# Sheet1.net
KiCad netlist of a schematic drawn in Altium Designer
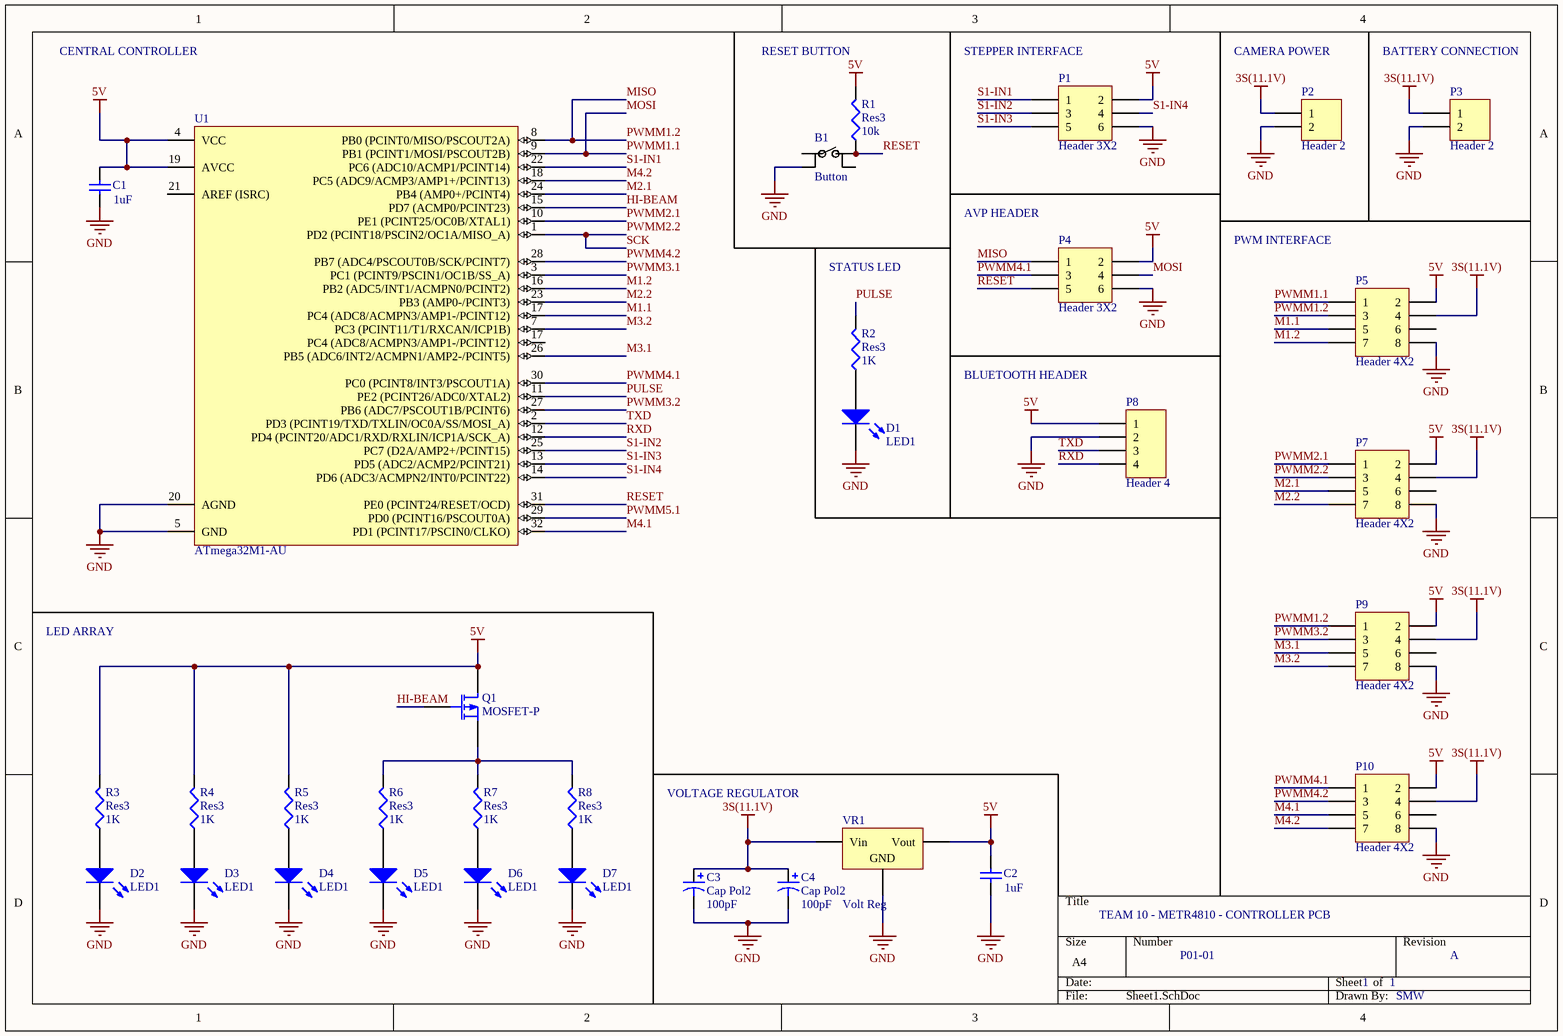
[diagram p0: Sheet1.SchDoc]

(export (version "E")
  (design (tool "Eeschema 10.0.6"))
  (components
    (comp (ref "B1")
      (value "Button")
      (footprint "SMT Tactile Button")
      (libsource (lib "WillsSchematicLibrary") (part "Switch"))
    )
    (comp (ref "C1")
      (value "1uF")
      (footprint "1608[0603]")
      (description "Capacitor")
      (fields (field (name "Comment") "Cap") (field (name "PUBLISHER") "Altium Limited"))
      (libsource (lib "Miscellaneous Devices") (part "Cap"))
    )
    (comp (ref "C2")
      (value "1uF")
      (footprint "1608[0603]")
      (description "Capacitor")
      (fields (field (name "Comment") "Cap") (field (name "PUBLISHER") "Altium Limited"))
      (libsource (lib "Miscellaneous Devices") (part "Cap"))
    )
    (comp (ref "C3")
      (value "Cap Pol2")
      (footprint "CAPAE9983X105M")
      (description "Polarized Capacitor (Axial)")
      (fields (field (name "ALTIUM_VALUE") "100pF") (field (name "PUBLISHER") "Altium Limited"))
      (libsource (lib "Miscellaneous Devices") (part "Cap Pol2"))
    )
    (comp (ref "C4")
      (value "Cap Pol2")
      (footprint "CAPAE9983X105M")
      (description "Polarized Capacitor (Axial)")
      (fields (field (name "ALTIUM_VALUE") "100pF") (field (name "PUBLISHER") "Altium Limited"))
      (libsource (lib "Miscellaneous Devices") (part "Cap Pol2"))
    )
    (comp (ref "D1")
      (value "LED1")
      (footprint "L0603")
      (description "Typical RED GaAs LED")
      (fields (field (name "PUBLISHER") "Altium Limited"))
      (libsource (lib "Miscellaneous Devices") (part "LED1"))
    )
    (comp (ref "D2")
      (value "LED1")
      (footprint "HDR1X2")
      (description "Typical RED GaAs LED")
      (fields (field (name "PUBLISHER") "Altium Limited"))
      (libsource (lib "Miscellaneous Devices") (part "LED1"))
    )
    (comp (ref "D3")
      (value "LED1")
      (footprint "HDR1X2")
      (description "Typical RED GaAs LED")
      (fields (field (name "PUBLISHER") "Altium Limited"))
      (libsource (lib "Miscellaneous Devices") (part "LED1"))
    )
    (comp (ref "D4")
      (value "LED1")
      (footprint "HDR1X2")
      (description "Typical RED GaAs LED")
      (fields (field (name "PUBLISHER") "Altium Limited"))
      (libsource (lib "Miscellaneous Devices") (part "LED1"))
    )
    (comp (ref "D5")
      (value "LED1")
      (footprint "HDR1X2")
      (description "Typical RED GaAs LED")
      (fields (field (name "PUBLISHER") "Altium Limited"))
      (libsource (lib "Miscellaneous Devices") (part "LED1"))
    )
    (comp (ref "D6")
      (value "LED1")
      (footprint "HDR1X2")
      (description "Typical RED GaAs LED")
      (fields (field (name "PUBLISHER") "Altium Limited"))
      (libsource (lib "Miscellaneous Devices") (part "LED1"))
    )
    (comp (ref "D7")
      (value "LED1")
      (footprint "HDR1X2")
      (description "Typical RED GaAs LED")
      (fields (field (name "PUBLISHER") "Altium Limited"))
      (libsource (lib "Miscellaneous Devices") (part "LED1"))
    )
    (comp (ref "P1")
      (value "Header 3X2")
      (footprint "HDR2X3")
      (description "Header, 3-Pin, Dual row")
      (fields (field (name "PUBLISHER") "Altium Limited"))
      (libsource (lib "Miscellaneous Connectors") (part "Header 3X2"))
    )
    (comp (ref "P2")
      (value "Header 2")
      (footprint "HDR1X2")
      (description "Header, 2-Pin")
      (fields (field (name "PUBLISHER") "Altium Limited"))
      (libsource (lib "Miscellaneous Connectors") (part "Header 2"))
    )
    (comp (ref "P3")
      (value "Header 2")
      (footprint "HDR1X2")
      (description "Header, 2-Pin")
      (fields (field (name "PUBLISHER") "Altium Limited"))
      (libsource (lib "Miscellaneous Connectors") (part "Header 2"))
    )
    (comp (ref "P4")
      (value "Header 3X2")
      (footprint "HDR2X3")
      (description "Header, 3-Pin, Dual row")
      (fields (field (name "PUBLISHER") "Altium Limited"))
      (libsource (lib "Miscellaneous Connectors") (part "Header 3X2"))
    )
    (comp (ref "P5")
      (value "Header 4X2")
      (footprint "HDR2X4")
      (description "Header, 4-Pin, Dual row")
      (fields (field (name "PUBLISHER") "Altium Limited"))
      (libsource (lib "Miscellaneous Connectors") (part "Header 4X2"))
    )
    (comp (ref "P7")
      (value "Header 4X2")
      (footprint "HDR2X4")
      (description "Header, 4-Pin, Dual row")
      (fields (field (name "PUBLISHER") "Altium Limited"))
      (libsource (lib "Miscellaneous Connectors") (part "Header 4X2"))
    )
    (comp (ref "P8")
      (value "Header 4")
      (footprint "HDR1X4")
      (description "Header, 4-Pin")
      (fields (field (name "PUBLISHER") "Altium Limited"))
      (libsource (lib "Miscellaneous Connectors") (part "Header 4"))
    )
    (comp (ref "P9")
      (value "Header 4X2")
      (footprint "HDR2X4")
      (description "Header, 4-Pin, Dual row")
      (fields (field (name "PUBLISHER") "Altium Limited"))
      (libsource (lib "Miscellaneous Connectors") (part "Header 4X2"))
    )
    (comp (ref "P10")
      (value "Header 4X2")
      (footprint "HDR2X4")
      (description "Header, 4-Pin, Dual row")
      (fields (field (name "PUBLISHER") "Altium Limited"))
      (libsource (lib "Miscellaneous Connectors") (part "Header 4X2"))
    )
    (comp (ref "Q1")
      (value "MOSFET-P")
      (footprint "SOT23-3")
      (description "P-Channel MOSFET")
      (fields (field (name "PUBLISHER") "Altium Limited"))
      (libsource (lib "Miscellaneous Devices") (part "MOSFET-P"))
    )
    (comp (ref "R1")
      (value "Res3")
      (footprint "J1-0603")
      (description "Resistor")
      (fields (field (name "ALTIUM_VALUE") "10k") (field (name "PUBLISHER") "Altium Limited"))
      (libsource (lib "Miscellaneous Devices") (part "Res3"))
    )
    (comp (ref "R2")
      (value "Res3")
      (footprint "J1-0603")
      (description "Resistor")
      (fields (field (name "ALTIUM_VALUE") "1K") (field (name "PUBLISHER") "Altium Limited"))
      (libsource (lib "Miscellaneous Devices") (part "Res3"))
    )
    (comp (ref "R3")
      (value "Res3")
      (footprint "J1-0603")
      (description "Resistor")
      (fields (field (name "ALTIUM_VALUE") "1K") (field (name "PUBLISHER") "Altium Limited"))
      (libsource (lib "Miscellaneous Devices") (part "Res3"))
    )
    (comp (ref "R4")
      (value "Res3")
      (footprint "J1-0603")
      (description "Resistor")
      (fields (field (name "ALTIUM_VALUE") "1K") (field (name "PUBLISHER") "Altium Limited"))
      (libsource (lib "Miscellaneous Devices") (part "Res3"))
    )
    (comp (ref "R5")
      (value "Res3")
      (footprint "J1-0603")
      (description "Resistor")
      (fields (field (name "ALTIUM_VALUE") "1K") (field (name "PUBLISHER") "Altium Limited"))
      (libsource (lib "Miscellaneous Devices") (part "Res3"))
    )
    (comp (ref "R6")
      (value "Res3")
      (footprint "J1-0603")
      (description "Resistor")
      (fields (field (name "ALTIUM_VALUE") "1K") (field (name "PUBLISHER") "Altium Limited"))
      (libsource (lib "Miscellaneous Devices") (part "Res3"))
    )
    (comp (ref "R7")
      (value "Res3")
      (footprint "J1-0603")
      (description "Resistor")
      (fields (field (name "ALTIUM_VALUE") "1K") (field (name "PUBLISHER") "Altium Limited"))
      (libsource (lib "Miscellaneous Devices") (part "Res3"))
    )
    (comp (ref "R8")
      (value "Res3")
      (footprint "J1-0603")
      (description "Resistor")
      (fields (field (name "ALTIUM_VALUE") "1K") (field (name "PUBLISHER") "Altium Limited"))
      (libsource (lib "Miscellaneous Devices") (part "Res3"))
    )
    (comp (ref "U1")
      (value "ATmega32M1-AU")
      (footprint "32A_L")
      (libsource (lib "Atmel Microcontroller AVR Automotive") (part "ATmega32M1-AU"))
    )
    (comp (ref "VR1")
      (value "Volt Reg")
      (footprint "D2PAK_N")
      (description "Voltage Regulator")
      (fields (field (name "PUBLISHER") "Altium Limited"))
      (libsource (lib "Miscellaneous Devices") (part "Volt Reg"))
    )
  )
  (nets
    (net (code "1") (name "/HI-BEAM") (class "Default")
      (node (ref "Q1") (pin "2") (pinfunction "G_2") (pintype "passive"))
      (node (ref "U1") (pin "15") (pinfunction "PD7_(ACMP0/PCINT23)_15") (pintype "bidirectional"))
    )
    (net (code "2") (name "/M1.1") (class "Default")
      (node (ref "P5") (pin "5") (pinfunction "5_5") (pintype "passive"))
      (node (ref "U1") (pin "17") (pinfunction "PC4_(ADC8/ACMPN3/AMP1-/PCINT12)_17") (pintype "bidirectional"))
    )
    (net (code "3") (name "/M1.2") (class "Default")
      (node (ref "P5") (pin "7") (pinfunction "7_7") (pintype "passive"))
      (node (ref "U1") (pin "16") (pinfunction "PB2_(ADC5/INT1/ACMPN0/PCINT2)_16") (pintype "bidirectional"))
    )
    (net (code "4") (name "/M2.1") (class "Default")
      (node (ref "P7") (pin "5") (pinfunction "5_5") (pintype "passive"))
      (node (ref "U1") (pin "24") (pinfunction "PB4_(AMP0+/PCINT4)_24") (pintype "bidirectional"))
    )
    (net (code "5") (name "/M2.2") (class "Default")
      (node (ref "P7") (pin "7") (pinfunction "7_7") (pintype "passive"))
      (node (ref "U1") (pin "23") (pinfunction "PB3_(AMP0-/PCINT3)_23") (pintype "bidirectional"))
    )
    (net (code "6") (name "/M3.1") (class "Default")
      (node (ref "P9") (pin "5") (pinfunction "5_5") (pintype "passive"))
      (node (ref "U1") (pin "26") (pinfunction "PB5_(ADC6/INT2/ACMPN1/AMP2-/PCINT5)_26") (pintype "bidirectional"))
    )
    (net (code "7") (name "/M3.2") (class "Default")
      (node (ref "P9") (pin "7") (pinfunction "7_7") (pintype "passive"))
      (node (ref "U1") (pin "7") (pinfunction "PC3_(PCINT11/T1/RXCAN/ICP1B)_7") (pintype "bidirectional"))
    )
    (net (code "8") (name "/M4.1") (class "Default")
      (node (ref "P10") (pin "5") (pinfunction "5_5") (pintype "passive"))
      (node (ref "U1") (pin "32") (pinfunction "PD1_(PCINT17/PSCIN0/CLKO)_32") (pintype "bidirectional"))
    )
    (net (code "9") (name "/M4.2") (class "Default")
      (node (ref "P10") (pin "7") (pinfunction "7_7") (pintype "passive"))
      (node (ref "U1") (pin "18") (pinfunction "PC5_(ADC9/ACMP3/AMP1+/PCINT13)_18") (pintype "bidirectional"))
    )
    (net (code "10") (name "/MISO") (class "Default")
      (node (ref "P4") (pin "1") (pinfunction "1_1") (pintype "passive"))
      (node (ref "P5") (pin "3") (pinfunction "3_3") (pintype "passive"))
      (node (ref "P9") (pin "1") (pinfunction "1_1") (pintype "passive"))
      (node (ref "U1") (pin "8") (pinfunction "PB0_(PCINT0/MISO/PSCOUT2A)_8") (pintype "bidirectional"))
    )
    (net (code "11") (name "/MOSI") (class "Default")
      (node (ref "P4") (pin "4") (pinfunction "4_4") (pintype "passive"))
      (node (ref "P5") (pin "1") (pinfunction "1_1") (pintype "passive"))
      (node (ref "U1") (pin "9") (pinfunction "PB1_(PCINT1/MOSI/PSCOUT2B)_9") (pintype "bidirectional"))
    )
    (net (code "12") (name "/PULSE") (class "Default")
      (node (ref "R2") (pin "2") (pinfunction "2_2") (pintype "passive"))
      (node (ref "U1") (pin "11") (pinfunction "PE2_(PCINT26/ADC0/XTAL2)_11") (pintype "bidirectional"))
    )
    (net (code "13") (name "/PWMM2.1") (class "Default")
      (node (ref "P7") (pin "1") (pinfunction "1_1") (pintype "passive"))
      (node (ref "U1") (pin "10") (pinfunction "PE1_(PCINT25/OC0B/XTAL1)_10") (pintype "bidirectional"))
    )
    (net (code "14") (name "/PWMM2.2") (class "Default")
      (node (ref "P7") (pin "3") (pinfunction "3_3") (pintype "passive"))
      (node (ref "U1") (pin "1") (pinfunction "PD2_(PCINT18/PSCIN2/OC1A/MISO_A)_1") (pintype "bidirectional"))
    )
    (net (code "15") (name "/PWMM3.1") (class "Default")
      (node (ref "U1") (pin "3") (pinfunction "PC1_(PCINT9/PSCIN1/OC1B/SS_A)_3") (pintype "bidirectional"))
    )
    (net (code "16") (name "/PWMM3.2") (class "Default")
      (node (ref "P9") (pin "3") (pinfunction "3_3") (pintype "passive"))
      (node (ref "U1") (pin "27") (pinfunction "PB6_(ADC7/PSCOUT1B/PCINT6)_27") (pintype "bidirectional"))
    )
    (net (code "17") (name "/PWMM4.1") (class "Default")
      (node (ref "P10") (pin "1") (pinfunction "1_1") (pintype "passive"))
      (node (ref "P4") (pin "3") (pinfunction "3_3") (pintype "passive"))
      (node (ref "U1") (pin "30") (pinfunction "PC0_(PCINT8/INT3/PSCOUT1A)_30") (pintype "bidirectional"))
    )
    (net (code "18") (name "/PWMM4.2") (class "Default")
      (node (ref "P10") (pin "3") (pinfunction "3_3") (pintype "passive"))
      (node (ref "U1") (pin "28") (pinfunction "PB7_(ADC4/PSCOUT0B/SCK/PCINT7)_28") (pintype "bidirectional"))
    )
    (net (code "19") (name "/PWMM5.1") (class "Default")
      (node (ref "U1") (pin "29") (pinfunction "PD0_(PCINT16/PSCOUT0A)_29") (pintype "bidirectional"))
    )
    (net (code "20") (name "/RESET") (class "Default")
      (node (ref "B1") (pin "4") (pinfunction "4_4") (pintype "passive"))
      (node (ref "P4") (pin "5") (pinfunction "5_5") (pintype "passive"))
      (node (ref "R1") (pin "1") (pinfunction "1_1") (pintype "passive"))
      (node (ref "U1") (pin "31") (pinfunction "PE0_(PCINT24/RESET/OCD)_31") (pintype "bidirectional"))
    )
    (net (code "21") (name "/RXD") (class "Default")
      (node (ref "P8") (pin "4") (pinfunction "4_4") (pintype "passive"))
      (node (ref "U1") (pin "12") (pinfunction "PD4_(PCINT20/ADC1/RXD/RXLIN/ICP1A/SCK_A)_12") (pintype "bidirectional"))
    )
    (net (code "22") (name "/S1-IN1") (class "Default")
      (node (ref "P1") (pin "1") (pinfunction "1_1") (pintype "passive"))
      (node (ref "U1") (pin "22") (pinfunction "PC6_(ADC10/ACMP1/PCINT14)_22") (pintype "bidirectional"))
    )
    (net (code "23") (name "/S1-IN2") (class "Default")
      (node (ref "P1") (pin "3") (pinfunction "3_3") (pintype "passive"))
      (node (ref "U1") (pin "25") (pinfunction "PC7_(D2A/AMP2+/PCINT15)_25") (pintype "bidirectional"))
    )
    (net (code "24") (name "/S1-IN3") (class "Default")
      (node (ref "P1") (pin "5") (pinfunction "5_5") (pintype "passive"))
      (node (ref "U1") (pin "13") (pinfunction "PD5_(ADC2/ACMP2/PCINT21)_13") (pintype "bidirectional"))
    )
    (net (code "25") (name "/S1-IN4") (class "Default")
      (node (ref "P1") (pin "4") (pinfunction "4_4") (pintype "passive"))
      (node (ref "U1") (pin "14") (pinfunction "PD6_(ADC3/ACMPN2/INT0/PCINT22)_14") (pintype "bidirectional"))
    )
    (net (code "26") (name "/TXD") (class "Default")
      (node (ref "P8") (pin "3") (pinfunction "3_3") (pintype "passive"))
      (node (ref "U1") (pin "2") (pinfunction "PD3_(PCINT19/TXD/TXLIN/OC0A/SS/MOSI_A)_2") (pintype "bidirectional"))
    )
    (net (code "27") (name "3S(11.1V)") (class "Default")
      (node (ref "C3") (pin "1") (pinfunction "1_1") (pintype "passive"))
      (node (ref "C4") (pin "1") (pinfunction "1_1") (pintype "passive"))
      (node (ref "P10") (pin "4") (pinfunction "4_4") (pintype "passive"))
      (node (ref "P2") (pin "1") (pinfunction "1_1") (pintype "passive"))
      (node (ref "P3") (pin "1") (pinfunction "1_1") (pintype "passive"))
      (node (ref "P5") (pin "4") (pinfunction "4_4") (pintype "passive"))
      (node (ref "P7") (pin "4") (pinfunction "4_4") (pintype "passive"))
      (node (ref "P9") (pin "4") (pinfunction "4_4") (pintype "passive"))
      (node (ref "VR1") (pin "1") (pinfunction "Vin_1") (pintype "passive"))
    )
    (net (code "28") (name "5V") (class "Default")
      (node (ref "C1") (pin "2") (pinfunction "2_2") (pintype "passive"))
      (node (ref "C2") (pin "2") (pinfunction "2_2") (pintype "passive"))
      (node (ref "P1") (pin "2") (pinfunction "2_2") (pintype "passive"))
      (node (ref "P10") (pin "2") (pinfunction "2_2") (pintype "passive"))
      (node (ref "P4") (pin "2") (pinfunction "2_2") (pintype "passive"))
      (node (ref "P5") (pin "2") (pinfunction "2_2") (pintype "passive"))
      (node (ref "P7") (pin "2") (pinfunction "2_2") (pintype "passive"))
      (node (ref "P8") (pin "1") (pinfunction "1_1") (pintype "passive"))
      (node (ref "P9") (pin "2") (pinfunction "2_2") (pintype "passive"))
      (node (ref "Q1") (pin "1") (pinfunction "D_1") (pintype "passive"))
      (node (ref "R1") (pin "2") (pinfunction "2_2") (pintype "passive"))
      (node (ref "R3") (pin "2") (pinfunction "2_2") (pintype "passive"))
      (node (ref "R4") (pin "2") (pinfunction "2_2") (pintype "passive"))
      (node (ref "R5") (pin "2") (pinfunction "2_2") (pintype "passive"))
      (node (ref "U1") (pin "19") (pinfunction "AVCC_19") (pintype "power_in"))
      (node (ref "U1") (pin "4") (pinfunction "VCC_4") (pintype "power_in"))
      (node (ref "VR1") (pin "3") (pinfunction "Vout_3") (pintype "passive"))
    )
    (net (code "29") (name "GND") (class "Default")
      (node (ref "B1") (pin "2") (pinfunction "2_2") (pintype "passive"))
      (node (ref "C1") (pin "1") (pinfunction "1_1") (pintype "passive"))
      (node (ref "C2") (pin "1") (pinfunction "1_1") (pintype "passive"))
      (node (ref "C3") (pin "2") (pinfunction "2_2") (pintype "passive"))
      (node (ref "C4") (pin "2") (pinfunction "2_2") (pintype "passive"))
      (node (ref "D1") (pin "2") (pinfunction "K_2") (pintype "passive"))
      (node (ref "D2") (pin "2") (pinfunction "K_2") (pintype "passive"))
      (node (ref "D3") (pin "2") (pinfunction "K_2") (pintype "passive"))
      (node (ref "D4") (pin "2") (pinfunction "K_2") (pintype "passive"))
      (node (ref "D5") (pin "2") (pinfunction "K_2") (pintype "passive"))
      (node (ref "D6") (pin "2") (pinfunction "K_2") (pintype "passive"))
      (node (ref "D7") (pin "2") (pinfunction "K_2") (pintype "passive"))
      (node (ref "P1") (pin "6") (pinfunction "6_6") (pintype "passive"))
      (node (ref "P10") (pin "8") (pinfunction "8_8") (pintype "passive"))
      (node (ref "P2") (pin "2") (pinfunction "2_2") (pintype "passive"))
      (node (ref "P3") (pin "2") (pinfunction "2_2") (pintype "passive"))
      (node (ref "P4") (pin "6") (pinfunction "6_6") (pintype "passive"))
      (node (ref "P5") (pin "8") (pinfunction "8_8") (pintype "passive"))
      (node (ref "P7") (pin "8") (pinfunction "8_8") (pintype "passive"))
      (node (ref "P8") (pin "2") (pinfunction "2_2") (pintype "passive"))
      (node (ref "P9") (pin "8") (pinfunction "8_8") (pintype "passive"))
      (node (ref "U1") (pin "20") (pinfunction "AGND_20") (pintype "power_in"))
      (node (ref "U1") (pin "5") (pinfunction "GND_5") (pintype "power_in"))
      (node (ref "VR1") (pin "2") (pinfunction "GND_2") (pintype "passive"))
    )
    (net (code "30") (name "Net-(D1-A)") (class "Default")
      (node (ref "D1") (pin "1") (pinfunction "A_1") (pintype "passive"))
      (node (ref "R2") (pin "1") (pinfunction "1_1") (pintype "passive"))
    )
    (net (code "31") (name "Net-(D2-A)") (class "Default")
      (node (ref "D2") (pin "1") (pinfunction "A_1") (pintype "passive"))
      (node (ref "R3") (pin "1") (pinfunction "1_1") (pintype "passive"))
    )
    (net (code "32") (name "Net-(D3-A)") (class "Default")
      (node (ref "D3") (pin "1") (pinfunction "A_1") (pintype "passive"))
      (node (ref "R4") (pin "1") (pinfunction "1_1") (pintype "passive"))
    )
    (net (code "33") (name "Net-(D4-A)") (class "Default")
      (node (ref "D4") (pin "1") (pinfunction "A_1") (pintype "passive"))
      (node (ref "R5") (pin "1") (pinfunction "1_1") (pintype "passive"))
    )
    (net (code "34") (name "Net-(D5-A)") (class "Default")
      (node (ref "D5") (pin "1") (pinfunction "A_1") (pintype "passive"))
      (node (ref "R6") (pin "1") (pinfunction "1_1") (pintype "passive"))
    )
    (net (code "35") (name "Net-(D6-A)") (class "Default")
      (node (ref "D6") (pin "1") (pinfunction "A_1") (pintype "passive"))
      (node (ref "R7") (pin "1") (pinfunction "1_1") (pintype "passive"))
    )
    (net (code "36") (name "Net-(D7-A)") (class "Default")
      (node (ref "D7") (pin "1") (pinfunction "A_1") (pintype "passive"))
      (node (ref "R8") (pin "1") (pinfunction "1_1") (pintype "passive"))
    )
    (net (code "37") (name "Net-(Q1-S)") (class "Default")
      (node (ref "Q1") (pin "3") (pinfunction "S_3") (pintype "passive"))
      (node (ref "R6") (pin "2") (pinfunction "2_2") (pintype "passive"))
      (node (ref "R7") (pin "2") (pinfunction "2_2") (pintype "passive"))
      (node (ref "R8") (pin "2") (pinfunction "2_2") (pintype "passive"))
    )
    (net (code "38") (name "unconnected-(B1-Pad1)") (class "Default")
      (node (ref "B1") (pin "1") (pinfunction "1_1") (pintype "passive"))
    )
    (net (code "39") (name "unconnected-(B1-Pad3)") (class "Default")
      (node (ref "B1") (pin "3") (pinfunction "3_3") (pintype "passive"))
    )
    (net (code "40") (name "unconnected-(P5-Pad6)") (class "Default")
      (node (ref "P5") (pin "6") (pinfunction "6_6") (pintype "passive"))
    )
    (net (code "41") (name "unconnected-(P7-Pad6)") (class "Default")
      (node (ref "P7") (pin "6") (pinfunction "6_6") (pintype "passive"))
    )
    (net (code "42") (name "unconnected-(P9-Pad6)") (class "Default")
      (node (ref "P9") (pin "6") (pinfunction "6_6") (pintype "passive"))
    )
    (net (code "43") (name "unconnected-(P10-Pad6)") (class "Default")
      (node (ref "P10") (pin "6") (pinfunction "6_6") (pintype "passive"))
    )
    (net (code "44") (name "unconnected-(U1-AREF_(ISRC)-Pad21)") (class "Default")
      (node (ref "U1") (pin "21") (pinfunction "AREF_(ISRC)_21") (pintype "power_in"))
    )
    (net (code "45") (name "unconnected-(U1-PC4_(ADC8{slash}ACMPN3{slash}AMP1-{slash}PCINT12)-Pad17)") (class "Default")
      (node (ref "U1") (pin "17") (pinfunction "PC4_(ADC8/ACMPN3/AMP1-/PCINT12)_17") (pintype "bidirectional"))
    )
  )
)
